# Thumbstick.net
KiCad netlist of a schematic drawn in Altium Designer
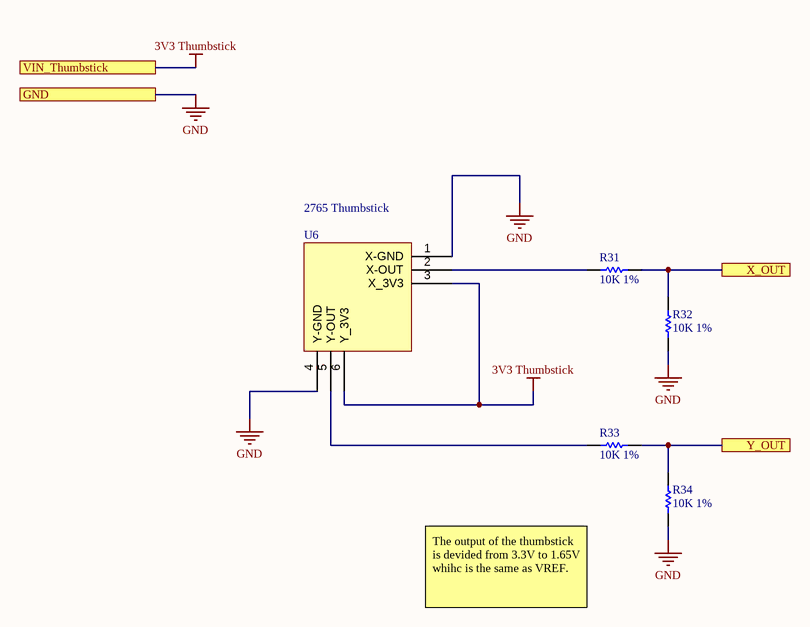
[diagram p0: Thumbstick.SchDoc]

(export (version "E")
  (design (tool "Eeschema 10.0.6"))
  (components
    (comp (ref "R31")
      (value "10K 1%")
      (footprint "RESC0603(1608)_N")
      (description "10K 0.1W 1% 0603 (1608 Metric)  SMD")
      (fields (field (name "POWER") "0.1 W") (field (name "TOLERANCE") "1 %"))
      (libsource (lib "Altium Content Vault") (part "RES"))
    )
    (comp (ref "R32")
      (value "10K 1%")
      (footprint "RESC0603(1608)_N")
      (description "10K 0.1W 1% 0603 (1608 Metric)  SMD")
      (fields (field (name "POWER") "0.1 W") (field (name "TOLERANCE") "1 %"))
      (libsource (lib "Altium Content Vault") (part "RES"))
    )
    (comp (ref "R33")
      (value "10K 1%")
      (footprint "RESC0603(1608)_N")
      (description "10K 0.1W 1% 0603 (1608 Metric)  SMD")
      (fields (field (name "POWER") "0.1 W") (field (name "TOLERANCE") "1 %"))
      (libsource (lib "Altium Content Vault") (part "RES"))
    )
    (comp (ref "R34")
      (value "10K 1%")
      (footprint "RESC0603(1608)_N")
      (description "10K 0.1W 1% 0603 (1608 Metric)  SMD")
      (fields (field (name "POWER") "0.1 W") (field (name "TOLERANCE") "1 %"))
      (libsource (lib "Altium Content Vault") (part "RES"))
    )
    (comp (ref "U6")
      (value "2765 Thumbstick")
      (footprint "thumbstick")
      (description "JOYSTICK 10K OHM 2 AXIS TH")
      (fields
        (field (name "MANUFACTURER") "Adafruit Industries")
        (field (name "MANUFACTURER PART NUMBER") "2765")
      )
      (libsource (lib "Thumbstick") (part "2765 Thumbstick"))
    )
  )
  (nets
    (net (code "1") (name "/X_OUT") (class "Default")
      (node (ref "R31") (pin "1") (pinfunction "1_1") (pintype "passive"))
      (node (ref "R32") (pin "2") (pinfunction "2_2") (pintype "passive"))
    )
    (net (code "2") (name "/Y_OUT") (class "Default")
      (node (ref "R33") (pin "1") (pinfunction "1_1") (pintype "passive"))
      (node (ref "R34") (pin "2") (pinfunction "2_2") (pintype "passive"))
    )
    (net (code "3") (name "3V3 Thumbstick") (class "Default")
      (node (ref "U6") (pin "3") (pinfunction "X_3V3_3") (pintype "passive"))
      (node (ref "U6") (pin "6") (pinfunction "Y_3V3_6") (pintype "passive"))
    )
    (net (code "4") (name "GND") (class "Default")
      (node (ref "R32") (pin "1") (pinfunction "1_1") (pintype "passive"))
      (node (ref "R34") (pin "1") (pinfunction "1_1") (pintype "passive"))
      (node (ref "U6") (pin "1") (pinfunction "X-GND_1") (pintype "passive"))
      (node (ref "U6") (pin "4") (pinfunction "Y-GND_4") (pintype "passive"))
    )
    (net (code "5") (name "Net-(U6-X-OUT)") (class "Default")
      (node (ref "R31") (pin "2") (pinfunction "2_2") (pintype "passive"))
      (node (ref "U6") (pin "2") (pinfunction "X-OUT_2") (pintype "passive"))
    )
    (net (code "6") (name "Net-(U6-Y-OUT)") (class "Default")
      (node (ref "R33") (pin "2") (pinfunction "2_2") (pintype "passive"))
      (node (ref "U6") (pin "5") (pinfunction "Y-OUT_5") (pintype "passive"))
    )
  )
)
